# ir.net
KiCad netlist of a schematic drawn in EAGLE
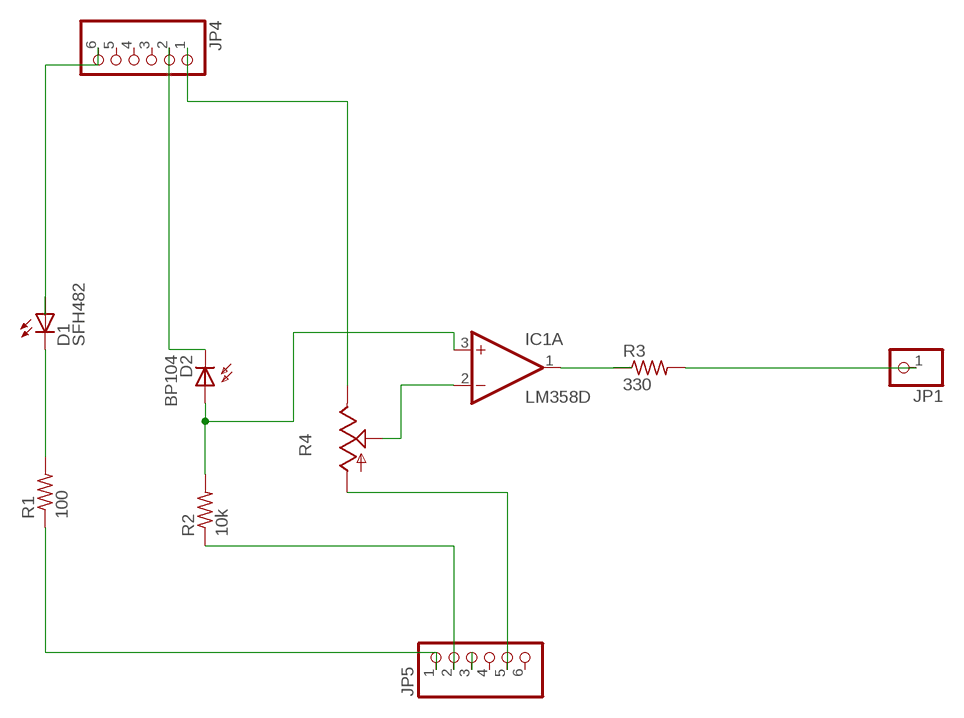
[diagram p0: schematic, sheet 1]

(export (version "E")
  (design (tool "Eeschema 10.0.6"))
  (components
    (comp (ref "D1")
      (value "SFH482")
      (footprint "eagle-import:SFH482")
      (libsource (lib "eagle-import") (part "SFH482"))
    )
    (comp (ref "D2")
      (value "BP104")
      (footprint "eagle-import:BP104")
      (fields (field (name "MF") "VISHAY/TELEFUNKEN"))
      (libsource (lib "eagle-import") (part "BP104"))
    )
    (comp (ref "IC1")
      (value "LM358D")
      (footprint "eagle-import:SO08")
      (libsource (lib "eagle-import") (part "LM358D"))
    )
    (comp (ref "JP1")
      (value "PINHD-1X1")
      (footprint "eagle-import:1X01")
      (libsource (lib "eagle-import") (part "PINHD-1X1"))
    )
    (comp (ref "JP4")
      (value "PINHD-1X6")
      (footprint "eagle-import:1X06")
      (libsource (lib "eagle-import") (part "PINHD-1X6"))
    )
    (comp (ref "JP5")
      (value "PINHD-1X6")
      (footprint "eagle-import:1X06")
      (libsource (lib "eagle-import") (part "PINHD-1X6"))
    )
    (comp (ref "R1")
      (value "100")
      (footprint "eagle-import:0204_7")
      (libsource (lib "eagle-import") (part "R-US_0204/7"))
    )
    (comp (ref "R2")
      (value "10k")
      (footprint "eagle-import:0204_7")
      (libsource (lib "eagle-import") (part "R-US_0204/7"))
    )
    (comp (ref "R3")
      (value "330")
      (footprint "eagle-import:0204_7")
      (libsource (lib "eagle-import") (part "R-US_0204/7"))
    )
    (comp (ref "R4")
      (value "TRIM_US-3223G")
      (footprint "eagle-import:3223G")
      (libsource (lib "eagle-import") (part "TRIM_US-3223G"))
    )
  )
  (nets
    (net (code "1") (name "Net-(D1-C)") (class "Default")
      (node (ref "D1") (pin "K") (pinfunction "C_K") (pintype "passive"))
      (node (ref "R1") (pin "2") (pinfunction "2_2") (pintype "passive"))
    )
    (net (code "2") (name "Net-(D1-PadA)") (class "Default")
      (node (ref "D1") (pin "A") (pinfunction "A_A") (pintype "passive"))
      (node (ref "JP4") (pin "6") (pinfunction "6_6") (pintype "passive"))
    )
    (net (code "3") (name "Net-(D2-C)") (class "Default")
      (node (ref "D2") (pin "K") (pinfunction "C_K") (pintype "passive"))
      (node (ref "JP4") (pin "2") (pinfunction "2_2") (pintype "passive"))
    )
    (net (code "4") (name "Net-(IC1A-+IN)") (class "Default")
      (node (ref "D2") (pin "A") (pinfunction "A_A") (pintype "passive"))
      (node (ref "IC1") (pin "3") (pinfunction "+IN_3") (pintype "input"))
      (node (ref "R2") (pin "2") (pinfunction "2_2") (pintype "passive"))
    )
    (net (code "5") (name "Net-(IC1A--IN)") (class "Default")
      (node (ref "IC1") (pin "2") (pinfunction "-IN_2") (pintype "input"))
      (node (ref "R4") (pin "2") (pinfunction "S_2") (pintype "passive"))
    )
    (net (code "6") (name "Net-(IC1A-OUT)") (class "Default")
      (node (ref "IC1") (pin "1") (pinfunction "OUT_1") (pintype "output"))
      (node (ref "R3") (pin "1") (pinfunction "1_1") (pintype "passive"))
    )
    (net (code "7") (name "Net-(JP1-Pad1)") (class "Default")
      (node (ref "JP1") (pin "1") (pinfunction "1_1") (pintype "passive"))
      (node (ref "R3") (pin "2") (pinfunction "2_2") (pintype "passive"))
    )
    (net (code "8") (name "Net-(JP5-Pad1)") (class "Default")
      (node (ref "JP5") (pin "1") (pinfunction "1_1") (pintype "passive"))
      (node (ref "R1") (pin "1") (pinfunction "1_1") (pintype "passive"))
    )
    (net (code "9") (name "Net-(JP5-Pad2)") (class "Default")
      (node (ref "JP5") (pin "2") (pinfunction "2_2") (pintype "passive"))
      (node (ref "R2") (pin "1") (pinfunction "1_1") (pintype "passive"))
    )
    (net (code "10") (name "Net-(R4-A)") (class "Default")
      (node (ref "JP5") (pin "5") (pinfunction "5_5") (pintype "passive"))
      (node (ref "R4") (pin "1") (pinfunction "A_1") (pintype "passive"))
    )
    (net (code "11") (name "Net-(R4-E)") (class "Default")
      (node (ref "JP4") (pin "1") (pinfunction "1_1") (pintype "passive"))
      (node (ref "R4") (pin "3") (pinfunction "E_3") (pintype "passive"))
    )
    (net (code "12") (name "unconnected-(JP4-Pad3)") (class "Default")
      (node (ref "JP4") (pin "3") (pinfunction "3_3") (pintype "passive"))
    )
    (net (code "13") (name "unconnected-(JP4-Pad4)") (class "Default")
      (node (ref "JP4") (pin "4") (pinfunction "4_4") (pintype "passive"))
    )
    (net (code "14") (name "unconnected-(JP4-Pad5)") (class "Default")
      (node (ref "JP4") (pin "5") (pinfunction "5_5") (pintype "passive"))
    )
    (net (code "15") (name "unconnected-(JP5-Pad3)") (class "Default")
      (node (ref "JP5") (pin "3") (pinfunction "3_3") (pintype "passive"))
    )
    (net (code "16") (name "unconnected-(JP5-Pad4)") (class "Default")
      (node (ref "JP5") (pin "4") (pinfunction "4_4") (pintype "passive"))
    )
    (net (code "17") (name "unconnected-(JP5-Pad6)") (class "Default")
      (node (ref "JP5") (pin "6") (pinfunction "6_6") (pintype "passive"))
    )
  )
)
